# upduino_v2_1_release.net
KiCad netlist of a schematic drawn in EAGLE
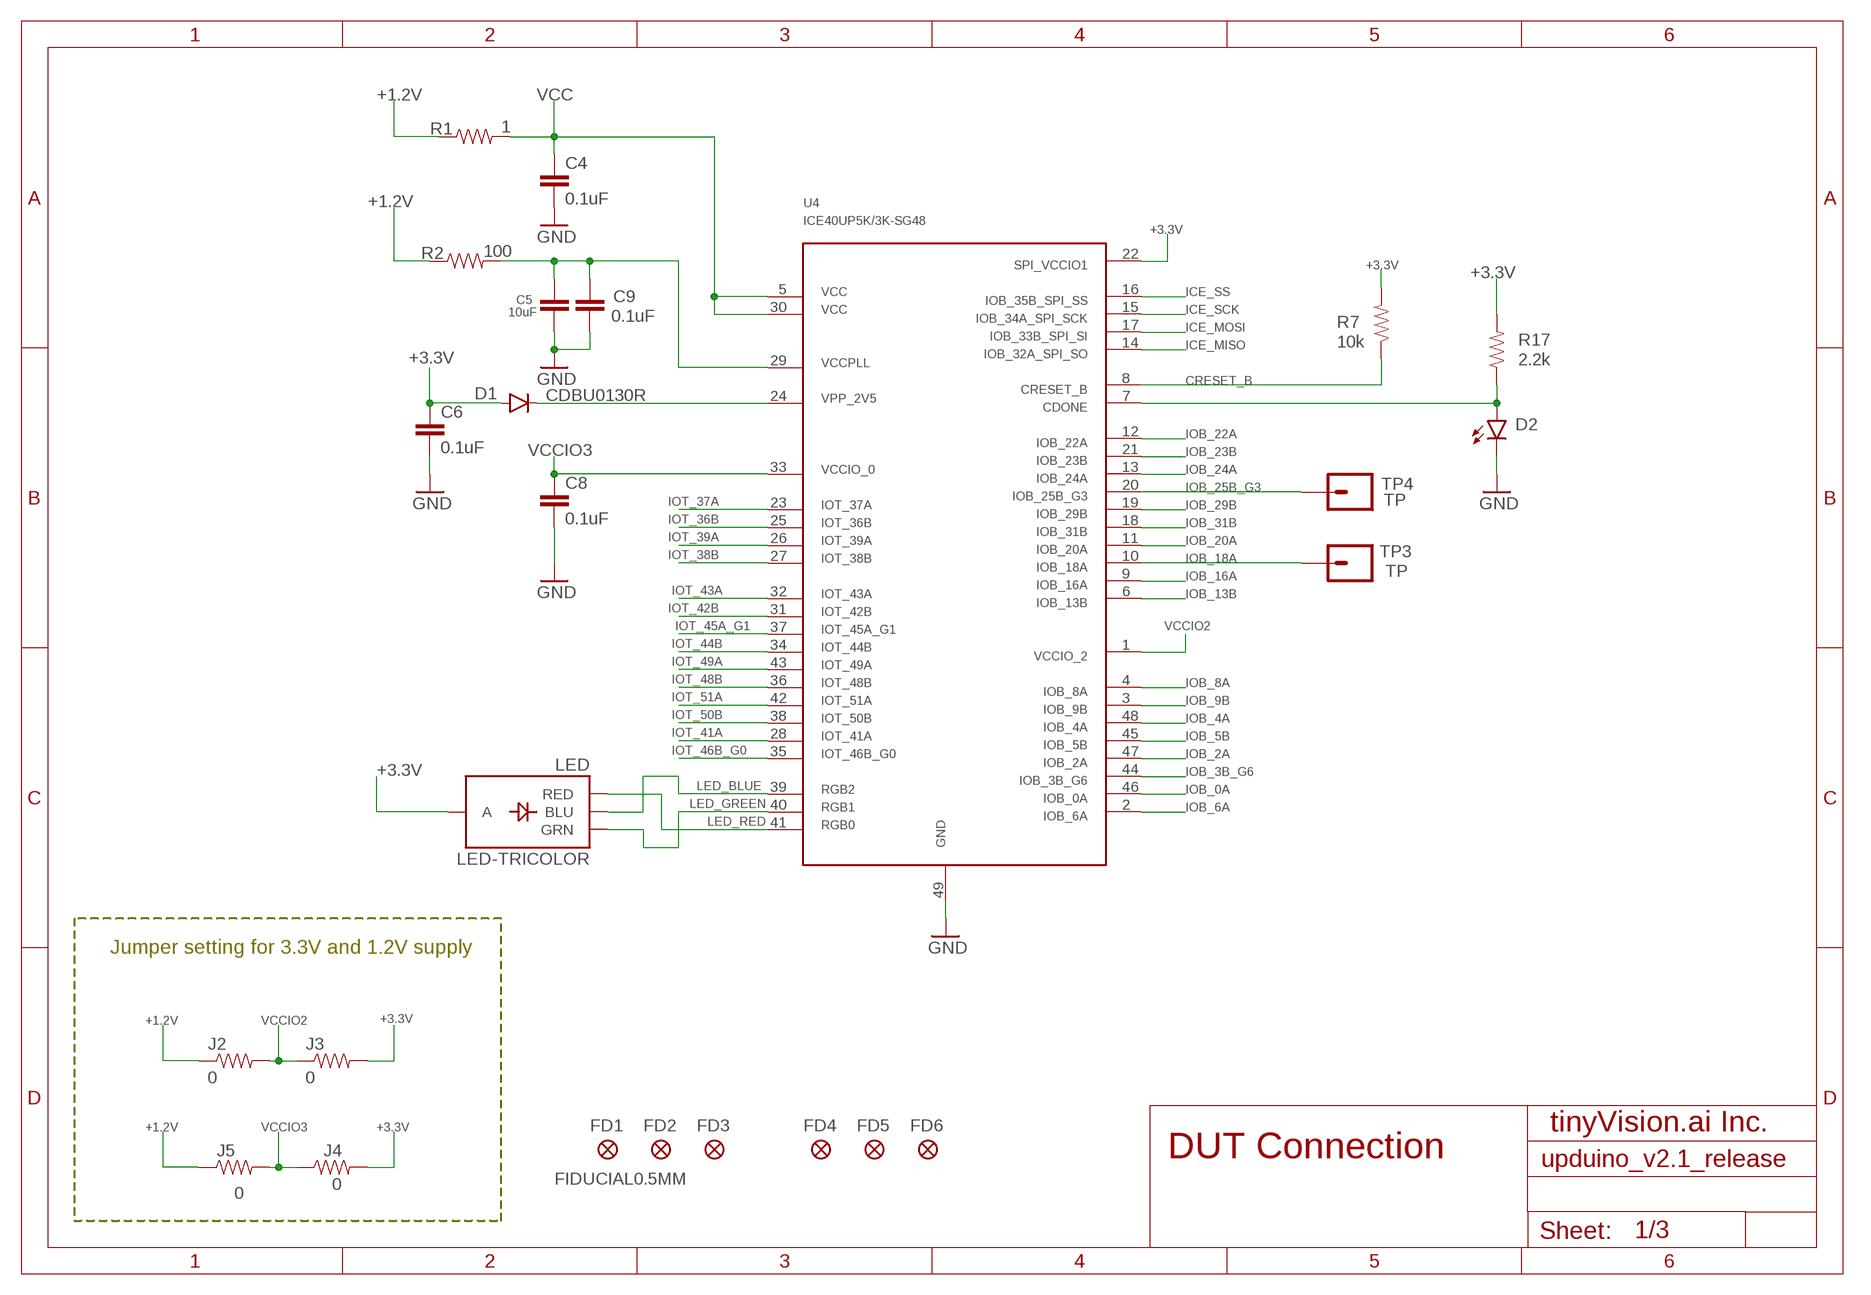
[diagram p0: schematic, sheet 1]
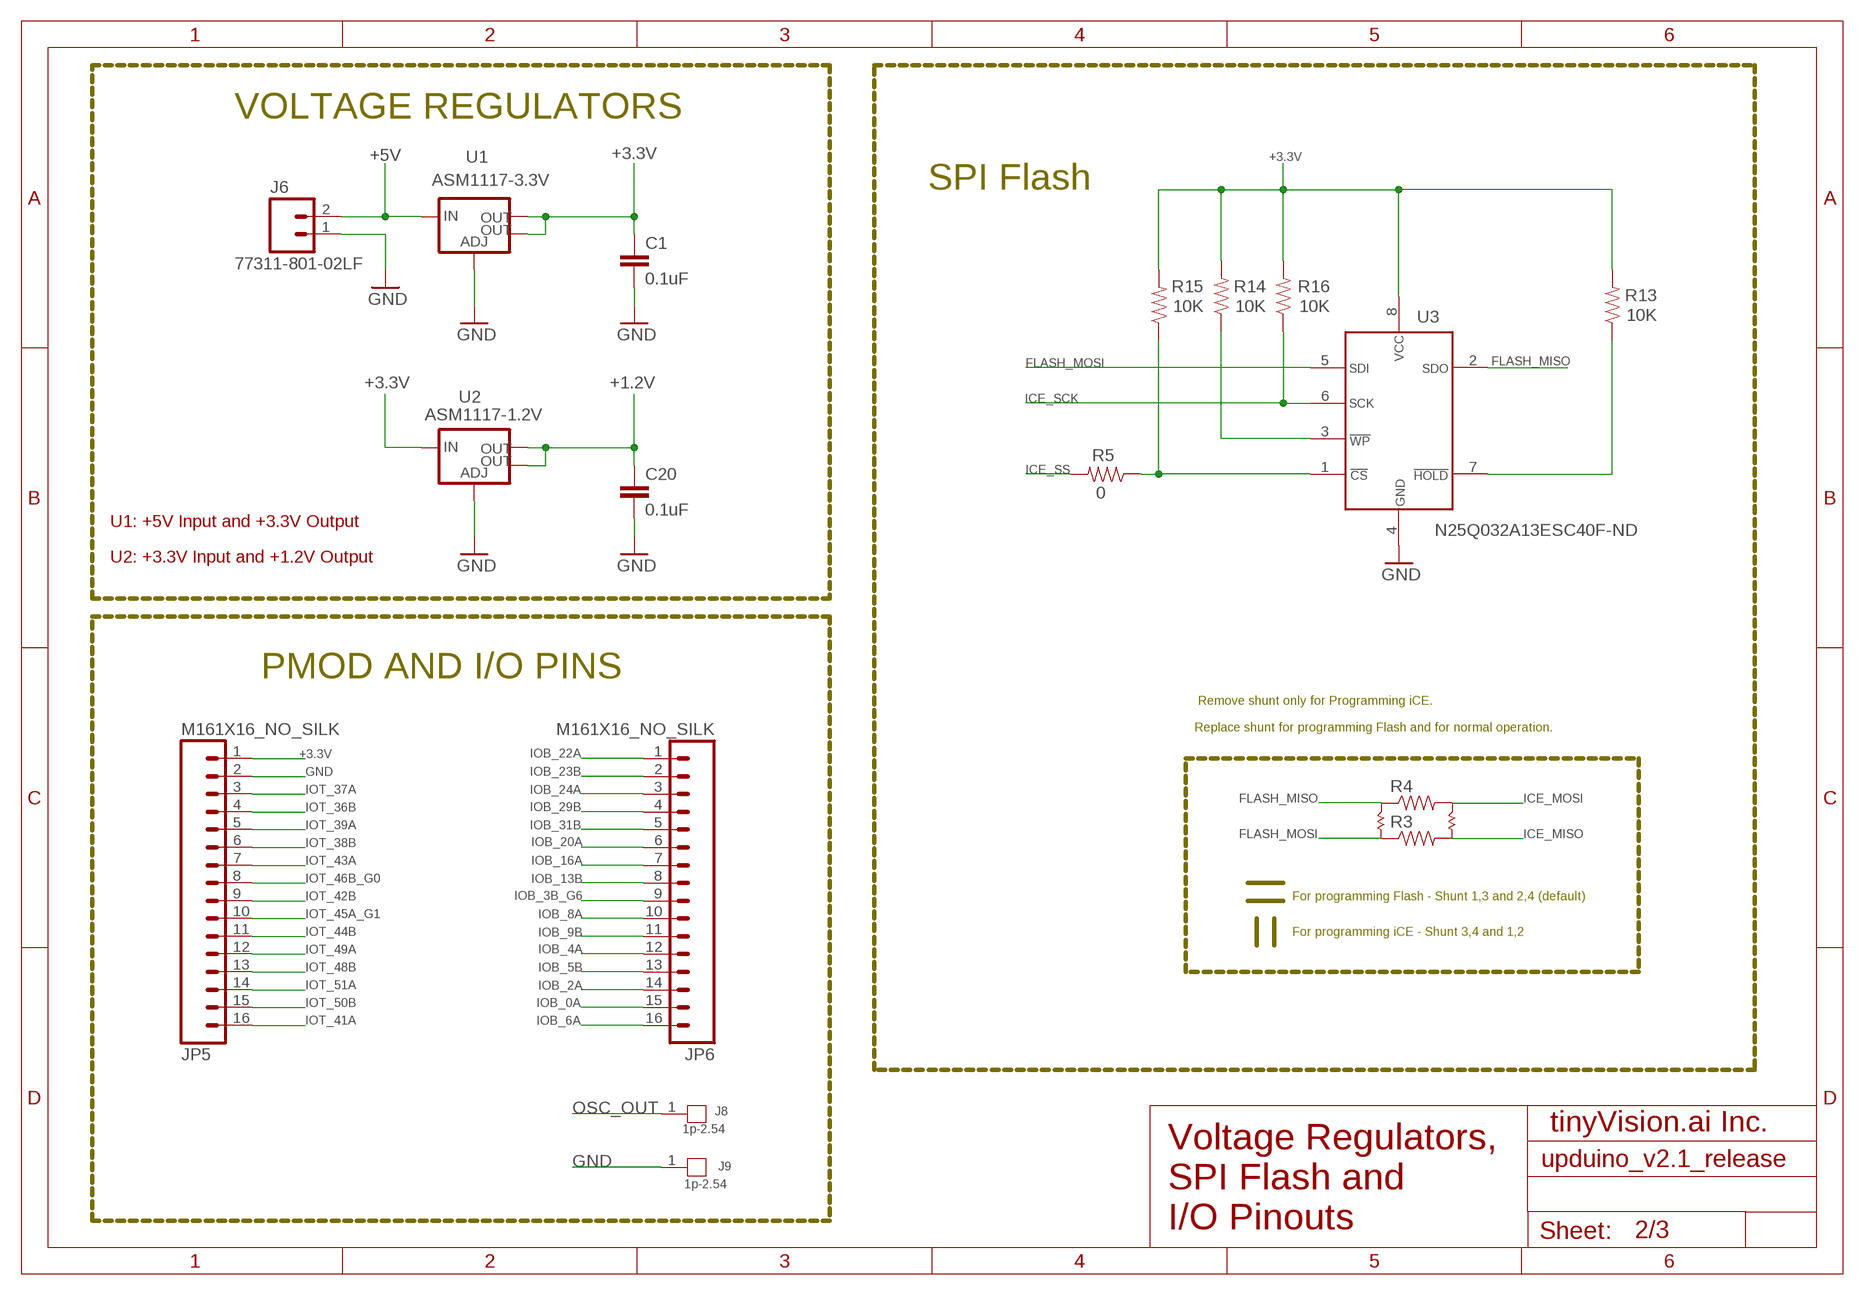
[diagram p1: schematic, sheet 2]
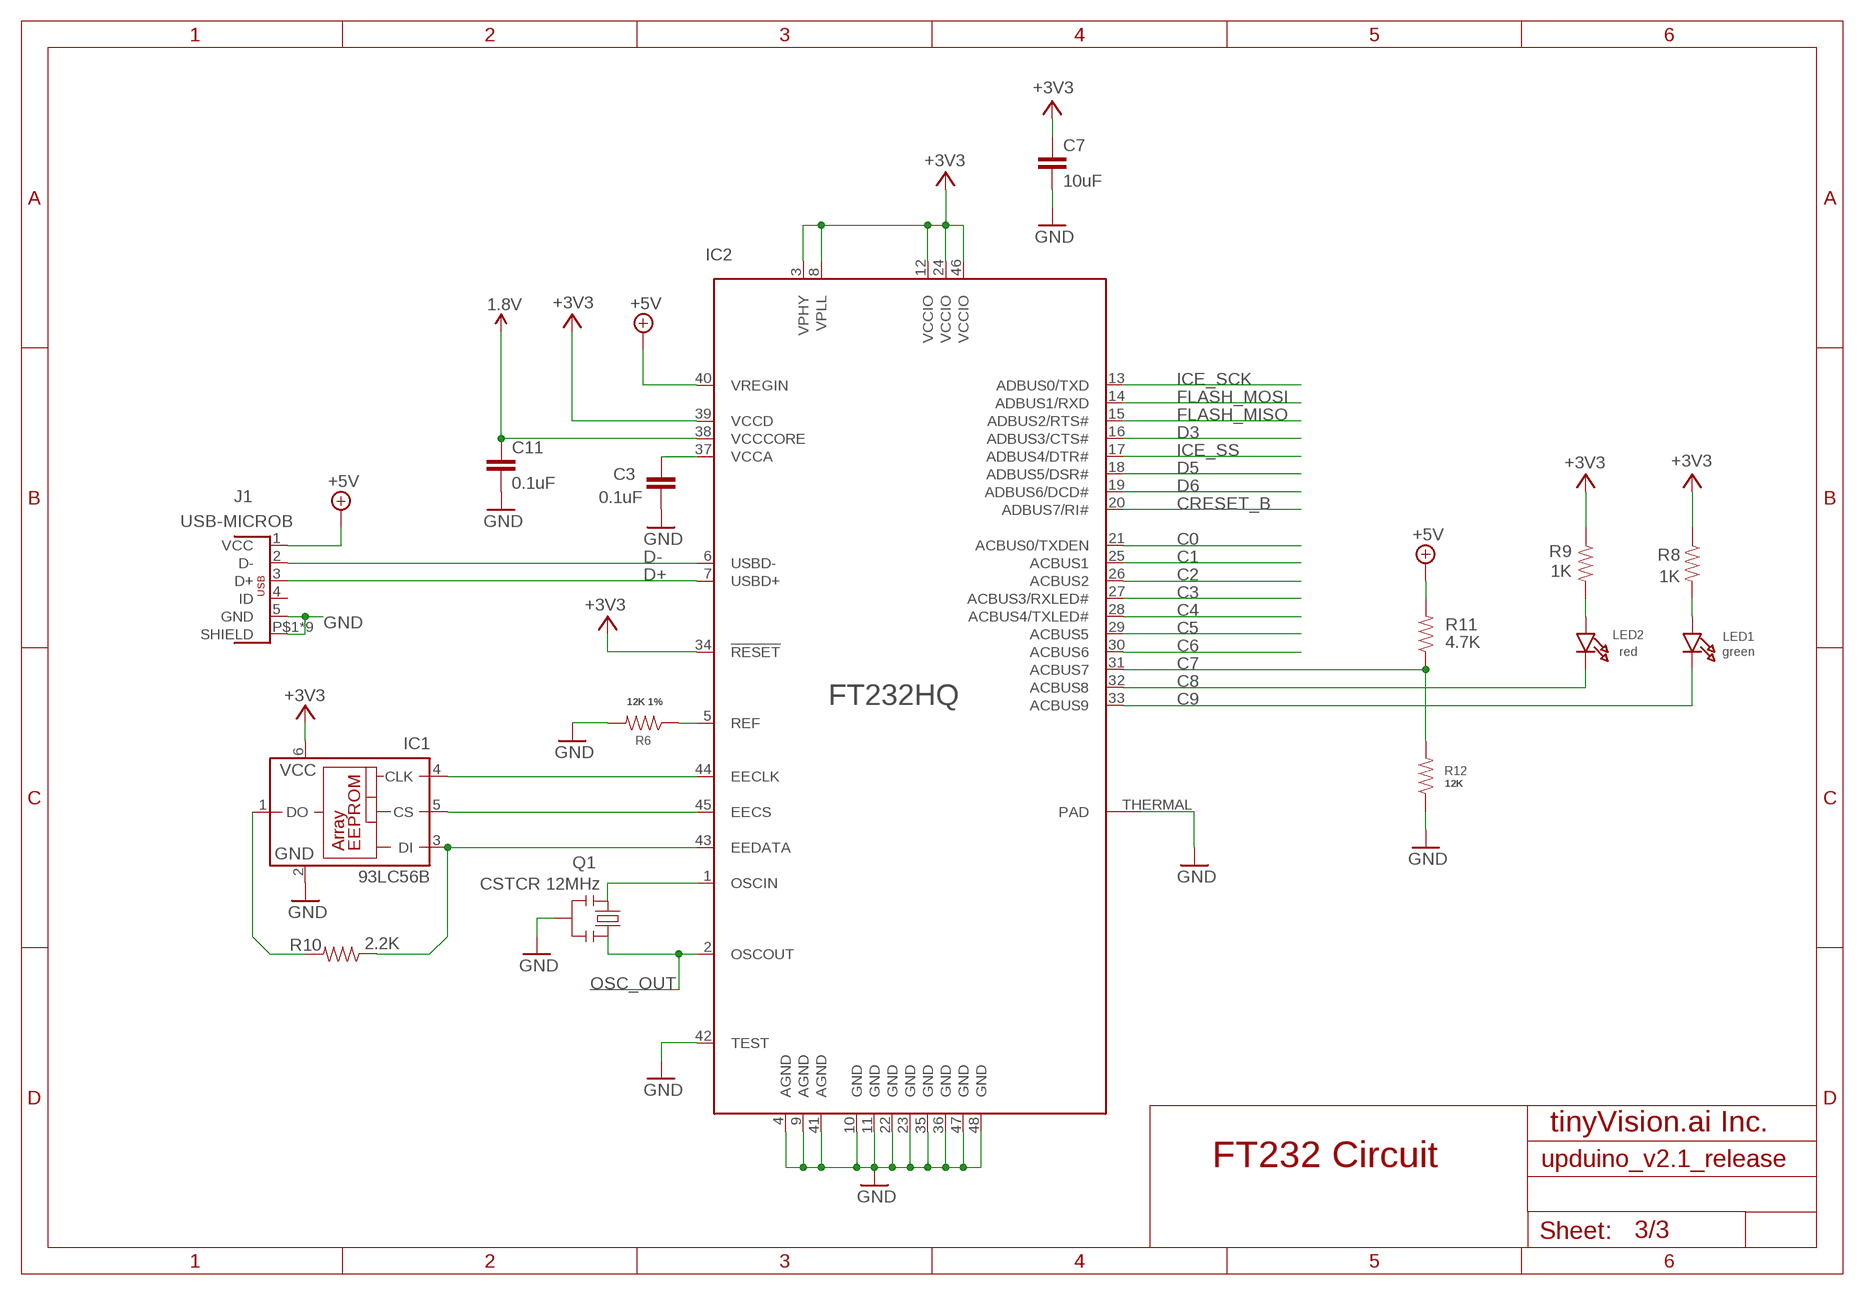
[diagram p2: schematic, sheet 3]

(export (version "E")
  (design (tool "Eeschema 10.0.6"))
  (components
    (comp (ref "C1")
      (value "0.1uF")
      (footprint "eagle-import:0603-CAP")
      (libsource (lib "eagle-import") (part "CAP0603-CAP"))
    )
    (comp (ref "C20")
      (value "0.1uF")
      (footprint "eagle-import:0603-CAP")
      (libsource (lib "eagle-import") (part "CAP0603-CAP"))
    )
    (comp (ref "J6")
      (value "77311-801-02LF")
      (footprint "eagle-import:1X02")
      (libsource (lib "eagle-import") (part "M02PTH"))
    )
    (comp (ref "J8")
      (value "1p-2.54")
      (footprint "eagle-import:1P-65_35MIL")
      (fields (field (name "MPN") "RF130-1013BBS0741"))
      (libsource (lib "eagle-import") (part "DIP-BLACK-ROUND-FEMALE-HEADER-VERT(1P-2.54)"))
    )
    (comp (ref "J9")
      (value "1p-2.54")
      (footprint "eagle-import:1P-65_35MIL")
      (fields (field (name "MPN") "RF130-1013BBS0741"))
      (libsource (lib "eagle-import") (part "DIP-BLACK-ROUND-FEMALE-HEADER-VERT(1P-2.54)"))
    )
    (comp (ref "JP5")
      (value "M161X16_NO_SILK")
      (footprint "eagle-import:1X16_NO_SILK")
      (libsource (lib "eagle-import") (part "M161X16_NO_SILK"))
    )
    (comp (ref "JP6")
      (value "M161X16_NO_SILK")
      (footprint "eagle-import:1X16_NO_SILK")
      (libsource (lib "eagle-import") (part "M161X16_NO_SILK"))
    )
    (comp (ref "R3")
      (value "RESISTOR0603")
      (footprint "eagle-import:0603-RES")
      (libsource (lib "eagle-import") (part "gtjennings_pcb_121217_1200_release_RESISTOR0603"))
    )
    (comp (ref "R4")
      (value "RESISTOR0603")
      (footprint "eagle-import:0603-RES")
      (libsource (lib "eagle-import") (part "gtjennings_pcb_121217_1200_release_RESISTOR0603"))
    )
    (comp (ref "R5")
      (value "0")
      (footprint "eagle-import:0603-RES")
      (libsource (lib "eagle-import") (part "gtjennings_pcb_121217_1200_release_RESISTOR0603"))
    )
    (comp (ref "R13")
      (value "10K")
      (footprint "eagle-import:0603-RES")
      (libsource (lib "eagle-import") (part "RESISTOR0603-RES"))
    )
    (comp (ref "R14")
      (value "10K")
      (footprint "eagle-import:0603-RES")
      (libsource (lib "eagle-import") (part "RESISTOR0603-RES"))
    )
    (comp (ref "R15")
      (value "10K")
      (footprint "eagle-import:0603-RES")
      (libsource (lib "eagle-import") (part "RESISTOR0603-RES"))
    )
    (comp (ref "R16")
      (value "10K")
      (footprint "eagle-import:0603-RES")
      (libsource (lib "eagle-import") (part "RESISTOR0603-RES"))
    )
    (comp (ref "U1")
      (value "ASM1117-3.3V")
      (footprint "eagle-import:SOT223")
      (libsource (lib "eagle-import") (part "V_REG_LM1117SOT223"))
    )
    (comp (ref "U2")
      (value "ASM1117-1.2V")
      (footprint "eagle-import:SOT223")
      (libsource (lib "eagle-import") (part "V_REG_LM1117SOT223"))
    )
    (comp (ref "U3")
      (value "N25Q032A13ESC40F-ND")
      (footprint "eagle-import:SO8")
      (fields (field (name "MPN") "N25Q032A13ESC40F-ND"))
      (libsource (lib "eagle-import") (part "N25Q032A13ESC40F-ND"))
    )
    (comp (ref "C3")
      (value "0.1uF")
      (footprint "eagle-import:0603-CAP")
      (libsource (lib "eagle-import") (part "CAP0603-CAP"))
    )
    (comp (ref "C7")
      (value "10uF")
      (footprint "eagle-import:0603-CAP")
      (libsource (lib "eagle-import") (part "CAP0603-CAP"))
    )
    (comp (ref "C11")
      (value "0.1uF")
      (footprint "eagle-import:0603-CAP")
      (libsource (lib "eagle-import") (part "CAP0603-CAP"))
    )
    (comp (ref "IC1")
      (value "93LC56B")
      (footprint "eagle-import:SOT23-6")
      (fields (field (name "MF") "MICROCHIP") (field (name "MPN") "93LC76AT-I/OT"))
      (libsource (lib "eagle-import") (part "9376?ALC"))
    )
    (comp (ref "IC2")
      (value "FT232HQ")
      (footprint "eagle-import:QFN48_8MM")
      (libsource (lib "eagle-import") (part "FT232HQ"))
    )
    (comp (ref "J1")
      (value "USB-MICROB")
      (footprint "eagle-import:USB_MICROB_10118194-0001LF")
      (libsource (lib "eagle-import") (part "USB-MICROB"))
    )
    (comp (ref "LED1")
      (value "green")
      (footprint "eagle-import:CHIPLED_0805_NOOUTLINE")
      (libsource (lib "eagle-import") (part "LED0805_NOOUTLINE"))
    )
    (comp (ref "LED2")
      (value "red")
      (footprint "eagle-import:CHIPLED_0805_NOOUTLINE")
      (libsource (lib "eagle-import") (part "LED0805_NOOUTLINE"))
    )
    (comp (ref "Q1")
      (value "CSTCR 12MHz")
      (footprint "eagle-import:RESONATOR-SMD")
      (libsource (lib "eagle-import") (part "RESONATORSMD"))
    )
    (comp (ref "R6")
      (value "12K 1%")
      (footprint "eagle-import:0603-RES")
      (libsource (lib "eagle-import") (part "gtjennings_pcb_121217_1200_release_RESISTOR0603"))
    )
    (comp (ref "R8")
      (value "1K")
      (footprint "eagle-import:0603-RES")
      (libsource (lib "eagle-import") (part "gtjennings_pcb_121217_1200_release_RESISTOR0603"))
    )
    (comp (ref "R9")
      (value "1K")
      (footprint "eagle-import:0603-RES")
      (libsource (lib "eagle-import") (part "gtjennings_pcb_121217_1200_release_RESISTOR0603"))
    )
    (comp (ref "R10")
      (value "2.2K")
      (footprint "eagle-import:0603-RES")
      (libsource (lib "eagle-import") (part "gtjennings_pcb_121217_1200_release_RESISTOR0603"))
    )
    (comp (ref "R11")
      (value "4.7K")
      (footprint "eagle-import:0603-RES")
      (libsource (lib "eagle-import") (part "gtjennings_pcb_121217_1200_release_RESISTOR0603"))
    )
    (comp (ref "R12")
      (value "12K")
      (footprint "eagle-import:0603-RES")
      (libsource (lib "eagle-import") (part "gtjennings_pcb_121217_1200_release_RESISTOR0603"))
    )
    (comp (ref "C4")
      (value "0.1uF")
      (footprint "eagle-import:0603-CAP")
      (libsource (lib "eagle-import") (part "CAP0603-CAP"))
    )
    (comp (ref "C5")
      (value "10uF")
      (footprint "eagle-import:0603-CAP")
      (libsource (lib "eagle-import") (part "CAP0603-CAP"))
    )
    (comp (ref "C6")
      (value "0.1uF")
      (footprint "eagle-import:0603-CAP")
      (libsource (lib "eagle-import") (part "CAP0603-CAP"))
    )
    (comp (ref "C8")
      (value "0.1uF")
      (footprint "eagle-import:0603-CAP")
      (libsource (lib "eagle-import") (part "CAP0603-CAP"))
    )
    (comp (ref "C9")
      (value "0.1uF")
      (footprint "eagle-import:0603-CAP")
      (libsource (lib "eagle-import") (part "CAP0603-CAP"))
    )
    (comp (ref "D1")
      (value "CDBU0130R")
      (footprint "eagle-import:SOD523")
      (libsource (lib "eagle-import") (part "DIODE1"))
    )
    (comp (ref "D2")
      (value "LED0603")
      (footprint "eagle-import:LED-0603")
      (libsource (lib "eagle-import") (part "LED0603"))
    )
    (comp (ref "FD1")
      (value "FIDUCIAL0.5MM")
      (footprint "eagle-import:FIDUCIAL_0.5MM")
      (libsource (lib "eagle-import") (part "FIDUCIAL0.5MM"))
    )
    (comp (ref "FD2")
      (value "FIDUCIAL0.5MM")
      (footprint "eagle-import:FIDUCIAL_0.5MM")
      (libsource (lib "eagle-import") (part "FIDUCIAL0.5MM"))
    )
    (comp (ref "FD3")
      (value "FIDUCIAL0.5MM")
      (footprint "eagle-import:FIDUCIAL_0.5MM")
      (libsource (lib "eagle-import") (part "FIDUCIAL0.5MM"))
    )
    (comp (ref "FD4")
      (value "FIDUCIAL0.5MM")
      (footprint "eagle-import:FIDUCIAL_0.5MM")
      (libsource (lib "eagle-import") (part "FIDUCIAL0.5MM"))
    )
    (comp (ref "FD5")
      (value "FIDUCIAL0.5MM")
      (footprint "eagle-import:FIDUCIAL_0.5MM")
      (libsource (lib "eagle-import") (part "FIDUCIAL0.5MM"))
    )
    (comp (ref "FD6")
      (value "FIDUCIAL0.5MM")
      (footprint "eagle-import:FIDUCIAL_0.5MM")
      (libsource (lib "eagle-import") (part "FIDUCIAL0.5MM"))
    )
    (comp (ref "J2")
      (value "0")
      (footprint "eagle-import:0603-RES")
      (libsource (lib "eagle-import") (part "RESISTOR0603-RES"))
    )
    (comp (ref "J3")
      (value "0")
      (footprint "eagle-import:0603-RES")
      (libsource (lib "eagle-import") (part "RESISTOR0603-RES"))
    )
    (comp (ref "J4")
      (value "0")
      (footprint "eagle-import:0603-RES")
      (libsource (lib "eagle-import") (part "RESISTOR0603-RES"))
    )
    (comp (ref "J5")
      (value "0")
      (footprint "eagle-import:0603-RES")
      (libsource (lib "eagle-import") (part "RESISTOR0603-RES"))
    )
    (comp (ref "LED")
      (value "LED-TRICOLOR")
      (footprint "eagle-import:LED-TRICOLOR-SMD")
      (libsource (lib "eagle-import") (part "LED-TRICOLOR"))
    )
    (comp (ref "R1")
      (value "1")
      (footprint "eagle-import:0603-RES")
      (libsource (lib "eagle-import") (part "RESISTOR0603-RES"))
    )
    (comp (ref "R2")
      (value "100")
      (footprint "eagle-import:0603-RES")
      (libsource (lib "eagle-import") (part "RESISTOR0603-RES"))
    )
    (comp (ref "R7")
      (value "10k")
      (footprint "eagle-import:0603-RES")
      (libsource (lib "eagle-import") (part "RESISTOR0603-RES"))
    )
    (comp (ref "R17")
      (value "2.2k")
      (footprint "eagle-import:0603-RES")
      (libsource (lib "eagle-import") (part "RESISTOR0603-RES"))
    )
    (comp (ref "TP3") (value "TP") (footprint "eagle-import:TP") (libsource (lib "eagle-import") (part "TP")))
    (comp (ref "TP4") (value "TP") (footprint "eagle-import:TP") (libsource (lib "eagle-import") (part "TP")))
    (comp (ref "U4")
      (value "ICE40UP5K/3K-SG48")
      (footprint "eagle-import:ICE40UP5K_3K-SG48")
      (libsource (lib "eagle-import") (part "ICE40UP5K/3K-SG48"))
    )
  )
  (nets
    (net (code "1") (name "+1.2V") (class "Default")
      (node (ref "C20") (pin "1") (pinfunction "1_1") (pintype "passive"))
      (node (ref "J2") (pin "1") (pinfunction "1_1") (pintype "passive"))
      (node (ref "J5") (pin "1") (pinfunction "1_1") (pintype "passive"))
      (node (ref "R1") (pin "1") (pinfunction "1_1") (pintype "passive"))
      (node (ref "R2") (pin "1") (pinfunction "1_1") (pintype "passive"))
      (node (ref "U2") (pin "2") (pinfunction "OUT_2") (pintype "output"))
      (node (ref "U2") (pin "4") (pinfunction "OUT_4") (pintype "output"))
    )
    (net (code "2") (name "+3.3V") (class "Default")
      (node (ref "C1") (pin "1") (pinfunction "1_1") (pintype "passive"))
      (node (ref "C6") (pin "1") (pinfunction "1_1") (pintype "passive"))
      (node (ref "D1") (pin "A") (pinfunction "A_A") (pintype "passive"))
      (node (ref "J3") (pin "2") (pinfunction "2_2") (pintype "passive"))
      (node (ref "J4") (pin "2") (pinfunction "2_2") (pintype "passive"))
      (node (ref "JP5") (pin "1") (pinfunction "1_1") (pintype "passive"))
      (node (ref "LED") (pin "A") (pinfunction "A_A") (pintype "bidirectional"))
      (node (ref "R13") (pin "2") (pinfunction "2_2") (pintype "passive"))
      (node (ref "R14") (pin "2") (pinfunction "2_2") (pintype "passive"))
      (node (ref "R15") (pin "2") (pinfunction "2_2") (pintype "passive"))
      (node (ref "R16") (pin "2") (pinfunction "2_2") (pintype "passive"))
      (node (ref "R17") (pin "2") (pinfunction "2_2") (pintype "passive"))
      (node (ref "R7") (pin "2") (pinfunction "2_2") (pintype "passive"))
      (node (ref "U1") (pin "2") (pinfunction "OUT_2") (pintype "output"))
      (node (ref "U1") (pin "4") (pinfunction "OUT_4") (pintype "output"))
      (node (ref "U2") (pin "3") (pinfunction "IN_3") (pintype "input"))
      (node (ref "U3") (pin "8") (pinfunction "8_8") (pintype "bidirectional"))
      (node (ref "U4") (pin "22") (pinfunction "22_22") (pintype "bidirectional"))
    )
    (net (code "3") (name "+3V3") (class "Default")
      (node (ref "C7") (pin "1") (pinfunction "1_1") (pintype "passive"))
      (node (ref "IC1") (pin "6") (pinfunction "VCC_6") (pintype "power_in"))
      (node (ref "IC2") (pin "12") (pinfunction "VCCIO_12") (pintype "power_in"))
      (node (ref "IC2") (pin "24") (pinfunction "VCCIO_24") (pintype "power_in"))
      (node (ref "IC2") (pin "3") (pinfunction "VPHY_3") (pintype "power_in"))
      (node (ref "IC2") (pin "34") (pinfunction "~{RESET}_34") (pintype "input"))
      (node (ref "IC2") (pin "39") (pinfunction "VCCD_39") (pintype "power_in"))
      (node (ref "IC2") (pin "46") (pinfunction "VCCIO_46") (pintype "power_in"))
      (node (ref "IC2") (pin "8") (pinfunction "VPLL_8") (pintype "power_in"))
      (node (ref "R8") (pin "1") (pinfunction "1_1") (pintype "passive"))
      (node (ref "R9") (pin "1") (pinfunction "1_1") (pintype "passive"))
    )
    (net (code "4") (name "+5V") (class "Default")
      (node (ref "IC2") (pin "40") (pinfunction "VREGIN_40") (pintype "power_in"))
      (node (ref "J1") (pin "1") (pinfunction "VCC_1") (pintype "bidirectional"))
      (node (ref "J6") (pin "2") (pinfunction "2_2") (pintype "passive"))
      (node (ref "R11") (pin "2") (pinfunction "2_2") (pintype "passive"))
      (node (ref "U1") (pin "3") (pinfunction "IN_3") (pintype "input"))
    )
    (net (code "5") (name "1.8V") (class "Default")
      (node (ref "C11") (pin "1") (pinfunction "1_1") (pintype "passive"))
      (node (ref "IC2") (pin "38") (pinfunction "VCCCORE_38") (pintype "power_in"))
    )
    (net (code "6") (name "C0") (class "Default")
      (node (ref "IC2") (pin "21") (pinfunction "ACBUS0/TXDEN_21") (pintype "bidirectional"))
    )
    (net (code "7") (name "C1") (class "Default")
      (node (ref "IC2") (pin "25") (pinfunction "ACBUS1_25") (pintype "bidirectional"))
    )
    (net (code "8") (name "C2") (class "Default")
      (node (ref "IC2") (pin "26") (pinfunction "ACBUS2_26") (pintype "bidirectional"))
    )
    (net (code "9") (name "C3") (class "Default")
      (node (ref "IC2") (pin "27") (pinfunction "ACBUS3/RXLED#_27") (pintype "bidirectional"))
    )
    (net (code "10") (name "C4") (class "Default")
      (node (ref "IC2") (pin "28") (pinfunction "ACBUS4/TXLED#_28") (pintype "bidirectional"))
    )
    (net (code "11") (name "C5") (class "Default")
      (node (ref "IC2") (pin "29") (pinfunction "ACBUS5_29") (pintype "bidirectional"))
    )
    (net (code "12") (name "C6") (class "Default")
      (node (ref "IC2") (pin "30") (pinfunction "ACBUS6_30") (pintype "bidirectional"))
    )
    (net (code "13") (name "C7") (class "Default")
      (node (ref "IC2") (pin "31") (pinfunction "ACBUS7_31") (pintype "bidirectional"))
      (node (ref "R11") (pin "1") (pinfunction "1_1") (pintype "passive"))
      (node (ref "R12") (pin "2") (pinfunction "2_2") (pintype "passive"))
    )
    (net (code "14") (name "C8") (class "Default")
      (node (ref "IC2") (pin "32") (pinfunction "ACBUS8_32") (pintype "bidirectional"))
      (node (ref "LED2") (pin "C") (pinfunction "C_C") (pintype "passive"))
    )
    (net (code "15") (name "C9") (class "Default")
      (node (ref "IC2") (pin "33") (pinfunction "ACBUS9_33") (pintype "bidirectional"))
      (node (ref "LED1") (pin "C") (pinfunction "C_C") (pintype "passive"))
    )
    (net (code "16") (name "CRESET_B") (class "Default")
      (node (ref "IC2") (pin "20") (pinfunction "ADBUS7/RI#_20") (pintype "input"))
      (node (ref "R7") (pin "1") (pinfunction "1_1") (pintype "passive"))
      (node (ref "U4") (pin "8") (pinfunction "8_8") (pintype "bidirectional"))
    )
    (net (code "17") (name "D+") (class "Default")
      (node (ref "IC2") (pin "7") (pinfunction "USBD+_7") (pintype "bidirectional"))
      (node (ref "J1") (pin "3") (pinfunction "D+_3") (pintype "bidirectional"))
    )
    (net (code "18") (name "D-") (class "Default")
      (node (ref "IC2") (pin "6") (pinfunction "USBD-_6") (pintype "bidirectional"))
      (node (ref "J1") (pin "2") (pinfunction "D-_2") (pintype "bidirectional"))
    )
    (net (code "19") (name "D3") (class "Default")
      (node (ref "IC2") (pin "16") (pinfunction "ADBUS3/CTS#_16") (pintype "input"))
    )
    (net (code "20") (name "D5") (class "Default")
      (node (ref "IC2") (pin "18") (pinfunction "ADBUS5/DSR#_18") (pintype "input"))
    )
    (net (code "21") (name "D6") (class "Default")
      (node (ref "IC2") (pin "19") (pinfunction "ADBUS6/DCD#_19") (pintype "input"))
    )
    (net (code "22") (name "FLASH_MISO") (class "Default")
      (node (ref "IC2") (pin "15") (pinfunction "ADBUS2/RTS#_15") (pintype "output"))
      (node (ref "R4") (pin "1") (pinfunction "1_1") (pintype "passive"))
      (node (ref "U3") (pin "2") (pinfunction "2_2") (pintype "bidirectional"))
    )
    (net (code "23") (name "FLASH_MOSI") (class "Default")
      (node (ref "IC2") (pin "14") (pinfunction "ADBUS1/RXD_14") (pintype "input"))
      (node (ref "R3") (pin "1") (pinfunction "1_1") (pintype "passive"))
      (node (ref "U3") (pin "5") (pinfunction "5_5") (pintype "bidirectional"))
    )
    (net (code "24") (name "GND") (class "Default")
      (node (ref "C1") (pin "2") (pinfunction "2_2") (pintype "passive"))
      (node (ref "C11") (pin "2") (pinfunction "2_2") (pintype "passive"))
      (node (ref "C20") (pin "2") (pinfunction "2_2") (pintype "passive"))
      (node (ref "C3") (pin "2") (pinfunction "2_2") (pintype "passive"))
      (node (ref "C4") (pin "2") (pinfunction "2_2") (pintype "passive"))
      (node (ref "C5") (pin "2") (pinfunction "2_2") (pintype "passive"))
      (node (ref "C6") (pin "2") (pinfunction "2_2") (pintype "passive"))
      (node (ref "C7") (pin "2") (pinfunction "2_2") (pintype "passive"))
      (node (ref "C8") (pin "2") (pinfunction "2_2") (pintype "passive"))
      (node (ref "C9") (pin "2") (pinfunction "2_2") (pintype "passive"))
      (node (ref "D2") (pin "C") (pinfunction "C_C") (pintype "passive"))
      (node (ref "IC1") (pin "2") (pinfunction "GND_2") (pintype "power_in"))
      (node (ref "IC2") (pin "10") (pinfunction "GND_10") (pintype "power_in"))
      (node (ref "IC2") (pin "11") (pinfunction "GND_11") (pintype "power_in"))
      (node (ref "IC2") (pin "22") (pinfunction "GND_22") (pintype "power_in"))
      (node (ref "IC2") (pin "23") (pinfunction "GND_23") (pintype "power_in"))
      (node (ref "IC2") (pin "35") (pinfunction "GND_35") (pintype "power_in"))
      (node (ref "IC2") (pin "36") (pinfunction "GND_36") (pintype "power_in"))
      (node (ref "IC2") (pin "4") (pinfunction "AGND_4") (pintype "power_in"))
      (node (ref "IC2") (pin "41") (pinfunction "AGND_41") (pintype "power_in"))
      (node (ref "IC2") (pin "42") (pinfunction "TEST_42") (pintype "input"))
      (node (ref "IC2") (pin "47") (pinfunction "GND_47") (pintype "power_in"))
      (node (ref "IC2") (pin "48") (pinfunction "GND_48") (pintype "power_in"))
      (node (ref "IC2") (pin "9") (pinfunction "AGND_9") (pintype "power_in"))
      (node (ref "IC2") (pin "THERMAL") (pinfunction "PAD_THERMAL") (pintype "passive"))
      (node (ref "J1") (pin "5") (pinfunction "GND_5") (pintype "bidirectional"))
      (node (ref "J1") (pin "P$1") (pinfunction "SHIELD_P$1") (pintype "bidirectional"))
      (node (ref "J1") (pin "P$2") (pinfunction "SHIELD_P$2") (pintype "bidirectional"))
      (node (ref "J1") (pin "P$3") (pinfunction "SHIELD_P$3") (pintype "bidirectional"))
      (node (ref "J1") (pin "P$4") (pinfunction "SHIELD_P$4") (pintype "bidirectional"))
      (node (ref "J1") (pin "P$5") (pinfunction "SHIELD_P$5") (pintype "bidirectional"))
      (node (ref "J1") (pin "P@1") (pinfunction "SHIELD_P@1") (pintype "bidirectional"))
      (node (ref "J1") (pin "P@2") (pinfunction "SHIELD_P@2") (pintype "bidirectional"))
      (node (ref "J1") (pin "P@3") (pinfunction "SHIELD_P@3") (pintype "bidirectional"))
      (node (ref "J1") (pin "P@4") (pinfunction "SHIELD_P@4") (pintype "bidirectional"))
      (node (ref "J6") (pin "1") (pinfunction "1_1") (pintype "passive"))
      (node (ref "J9") (pin "1") (pinfunction "1_1") (pintype "bidirectional"))
      (node (ref "JP5") (pin "2") (pinfunction "2_2") (pintype "passive"))
      (node (ref "Q1") (pin "2") (pinfunction "2_2") (pintype "passive"))
      (node (ref "R12") (pin "1") (pinfunction "1_1") (pintype "passive"))
      (node (ref "R6") (pin "2") (pinfunction "2_2") (pintype "passive"))
      (node (ref "U1") (pin "1") (pinfunction "ADJ_1") (pintype "input"))
      (node (ref "U2") (pin "1") (pinfunction "ADJ_1") (pintype "input"))
      (node (ref "U3") (pin "4") (pinfunction "4_4") (pintype "bidirectional"))
      (node (ref "U4") (pin "49") (pinfunction "49_49") (pintype "bidirectional"))
    )
    (net (code "25") (name "ICE_MISO") (class "Default")
      (node (ref "R3") (pin "2") (pinfunction "2_2") (pintype "passive"))
      (node (ref "U4") (pin "14") (pinfunction "14_14") (pintype "bidirectional"))
    )
    (net (code "26") (name "ICE_MOSI") (class "Default")
      (node (ref "R4") (pin "2") (pinfunction "2_2") (pintype "passive"))
      (node (ref "U4") (pin "17") (pinfunction "17_17") (pintype "bidirectional"))
    )
    (net (code "27") (name "ICE_SCK") (class "Default")
      (node (ref "IC2") (pin "13") (pinfunction "ADBUS0/TXD_13") (pintype "output"))
      (node (ref "R16") (pin "1") (pinfunction "1_1") (pintype "passive"))
      (node (ref "U3") (pin "6") (pinfunction "6_6") (pintype "bidirectional"))
      (node (ref "U4") (pin "15") (pinfunction "15_15") (pintype "bidirectional"))
    )
    (net (code "28") (name "ICE_SS") (class "Default")
      (node (ref "IC2") (pin "17") (pinfunction "ADBUS4/DTR#_17") (pintype "output"))
      (node (ref "R5") (pin "2") (pinfunction "2_2") (pintype "passive"))
      (node (ref "U4") (pin "16") (pinfunction "16_16") (pintype "bidirectional"))
    )
    (net (code "29") (name "IOB_0A") (class "Default")
      (node (ref "JP6") (pin "15") (pinfunction "15_15") (pintype "passive"))
      (node (ref "U4") (pin "46") (pinfunction "46_46") (pintype "bidirectional"))
    )
    (net (code "30") (name "IOB_2A") (class "Default")
      (node (ref "JP6") (pin "14") (pinfunction "14_14") (pintype "passive"))
      (node (ref "U4") (pin "47") (pinfunction "47_47") (pintype "bidirectional"))
    )
    (net (code "31") (name "IOB_3B_G6") (class "Default")
      (node (ref "JP6") (pin "9") (pinfunction "9_9") (pintype "passive"))
      (node (ref "U4") (pin "44") (pinfunction "44_44") (pintype "bidirectional"))
    )
    (net (code "32") (name "IOB_4A") (class "Default")
      (node (ref "JP6") (pin "12") (pinfunction "12_12") (pintype "passive"))
      (node (ref "U4") (pin "48") (pinfunction "48_48") (pintype "bidirectional"))
    )
    (net (code "33") (name "IOB_5B") (class "Default")
      (node (ref "JP6") (pin "13") (pinfunction "13_13") (pintype "passive"))
      (node (ref "U4") (pin "45") (pinfunction "45_45") (pintype "bidirectional"))
    )
    (net (code "34") (name "IOB_6A") (class "Default")
      (node (ref "JP6") (pin "16") (pinfunction "16_16") (pintype "passive"))
      (node (ref "U4") (pin "2") (pinfunction "2_2") (pintype "bidirectional"))
    )
    (net (code "35") (name "IOB_8A") (class "Default")
      (node (ref "JP6") (pin "10") (pinfunction "10_10") (pintype "passive"))
      (node (ref "U4") (pin "4") (pinfunction "4_4") (pintype "bidirectional"))
    )
    (net (code "36") (name "IOB_9B") (class "Default")
      (node (ref "JP6") (pin "11") (pinfunction "11_11") (pintype "passive"))
      (node (ref "U4") (pin "3") (pinfunction "3_3") (pintype "bidirectional"))
    )
    (net (code "37") (name "IOB_13B") (class "Default")
      (node (ref "JP6") (pin "8") (pinfunction "8_8") (pintype "passive"))
      (node (ref "U4") (pin "6") (pinfunction "6_6") (pintype "bidirectional"))
    )
    (net (code "38") (name "IOB_16A") (class "Default")
      (node (ref "JP6") (pin "7") (pinfunction "7_7") (pintype "passive"))
      (node (ref "U4") (pin "9") (pinfunction "9_9") (pintype "bidirectional"))
    )
    (net (code "39") (name "IOB_18A") (class "Default")
      (node (ref "TP3") (pin "1") (pinfunction "1_1") (pintype "passive"))
      (node (ref "U4") (pin "10") (pinfunction "10_10") (pintype "bidirectional"))
    )
    (net (code "40") (name "IOB_20A") (class "Default")
      (node (ref "JP6") (pin "6") (pinfunction "6_6") (pintype "passive"))
      (node (ref "U4") (pin "11") (pinfunction "11_11") (pintype "bidirectional"))
    )
    (net (code "41") (name "IOB_22A") (class "Default")
      (node (ref "JP6") (pin "1") (pinfunction "1_1") (pintype "passive"))
      (node (ref "U4") (pin "12") (pinfunction "12_12") (pintype "bidirectional"))
    )
    (net (code "42") (name "IOB_23B") (class "Default")
      (node (ref "JP6") (pin "2") (pinfunction "2_2") (pintype "passive"))
      (node (ref "U4") (pin "21") (pinfunction "21_21") (pintype "bidirectional"))
    )
    (net (code "43") (name "IOB_24A") (class "Default")
      (node (ref "JP6") (pin "3") (pinfunction "3_3") (pintype "passive"))
      (node (ref "U4") (pin "13") (pinfunction "13_13") (pintype "bidirectional"))
    )
    (net (code "44") (name "IOB_25B_G3") (class "Default")
      (node (ref "TP4") (pin "1") (pinfunction "1_1") (pintype "passive"))
      (node (ref "U4") (pin "20") (pinfunction "20_20") (pintype "bidirectional"))
    )
    (net (code "45") (name "IOB_29B") (class "Default")
      (node (ref "JP6") (pin "4") (pinfunction "4_4") (pintype "passive"))
      (node (ref "U4") (pin "19") (pinfunction "19_19") (pintype "bidirectional"))
    )
    (net (code "46") (name "IOB_31B") (class "Default")
      (node (ref "JP6") (pin "5") (pinfunction "5_5") (pintype "passive"))
      (node (ref "U4") (pin "18") (pinfunction "18_18") (pintype "bidirectional"))
    )
    (net (code "47") (name "IOT_36B") (class "Default")
      (node (ref "JP5") (pin "4") (pinfunction "4_4") (pintype "passive"))
      (node (ref "U4") (pin "25") (pinfunction "25_25") (pintype "bidirectional"))
    )
    (net (code "48") (name "IOT_37A") (class "Default")
      (node (ref "JP5") (pin "3") (pinfunction "3_3") (pintype "passive"))
      (node (ref "U4") (pin "23") (pinfunction "23_23") (pintype "bidirectional"))
    )
    (net (code "49") (name "IOT_38B") (class "Default")
      (node (ref "JP5") (pin "6") (pinfunction "6_6") (pintype "passive"))
      (node (ref "U4") (pin "27") (pinfunction "27_27") (pintype "bidirectional"))
    )
    (net (code "50") (name "IOT_39A") (class "Default")
      (node (ref "JP5") (pin "5") (pinfunction "5_5") (pintype "passive"))
      (node (ref "U4") (pin "26") (pinfunction "26_26") (pintype "bidirectional"))
    )
    (net (code "51") (name "IOT_41A") (class "Default")
      (node (ref "JP5") (pin "16") (pinfunction "16_16") (pintype "passive"))
      (node (ref "U4") (pin "28") (pinfunction "28_28") (pintype "bidirectional"))
    )
    (net (code "52") (name "IOT_42B") (class "Default")
      (node (ref "JP5") (pin "9") (pinfunction "9_9") (pintype "passive"))
      (node (ref "U4") (pin "31") (pinfunction "31_31") (pintype "bidirectional"))
    )
    (net (code "53") (name "IOT_43A") (class "Default")
      (node (ref "JP5") (pin "7") (pinfunction "7_7") (pintype "passive"))
      (node (ref "U4") (pin "32") (pinfunction "32_32") (pintype "bidirectional"))
    )
    (net (code "54") (name "IOT_44B") (class "Default")
      (node (ref "JP5") (pin "11") (pinfunction "11_11") (pintype "passive"))
      (node (ref "U4") (pin "34") (pinfunction "34_34") (pintype "bidirectional"))
    )
    (net (code "55") (name "IOT_45A_G1") (class "Default")
      (node (ref "JP5") (pin "10") (pinfunction "10_10") (pintype "passive"))
      (node (ref "U4") (pin "37") (pinfunction "37_37") (pintype "bidirectional"))
    )
    (net (code "56") (name "IOT_46B_G0") (class "Default")
      (node (ref "JP5") (pin "8") (pinfunction "8_8") (pintype "passive"))
      (node (ref "U4") (pin "35") (pinfunction "35_35") (pintype "bidirectional"))
    )
    (net (code "57") (name "IOT_48B") (class "Default")
      (node (ref "JP5") (pin "13") (pinfunction "13_13") (pintype "passive"))
      (node (ref "U4") (pin "36") (pinfunction "36_36") (pintype "bidirectional"))
    )
    (net (code "58") (name "IOT_49A") (class "Default")
      (node (ref "JP5") (pin "12") (pinfunction "12_12") (pintype "passive"))
      (node (ref "U4") (pin "43") (pinfunction "43_43") (pintype "bidirectional"))
    )
    (net (code "59") (name "IOT_50B") (class "Default")
      (node (ref "JP5") (pin "15") (pinfunction "15_15") (pintype "passive"))
      (node (ref "U4") (pin "38") (pinfunction "38_38") (pintype "bidirectional"))
    )
    (net (code "60") (name "IOT_51A") (class "Default")
      (node (ref "JP5") (pin "14") (pinfunction "14_14") (pintype "passive"))
      (node (ref "U4") (pin "42") (pinfunction "42_42") (pintype "bidirectional"))
    )
    (net (code "61") (name "LED_BLUE") (class "Default")
      (node (ref "LED") (pin "B") (pinfunction "BLU_B") (pintype "bidirectional"))
      (node (ref "U4") (pin "39") (pinfunction "39_39") (pintype "bidirectional"))
    )
    (net (code "62") (name "LED_GREEN") (class "Default")
      (node (ref "LED") (pin "G") (pinfunction "GRN_G") (pintype "bidirectional"))
      (node (ref "U4") (pin "40") (pinfunction "40_40") (pintype "bidirectional"))
    )
    (net (code "63") (name "LED_RED") (class "Default")
      (node (ref "LED") (pin "R") (pinfunction "RED_R") (pintype "bidirectional"))
      (node (ref "U4") (pin "41") (pinfunction "41_41") (pintype "bidirectional"))
    )
    (net (code "64") (name "Net-(C5-Pad1)") (class "Default")
      (node (ref "C5") (pin "1") (pinfunction "1_1") (pintype "passive"))
      (node (ref "C9") (pin "1") (pinfunction "1_1") (pintype "passive"))
      (node (ref "R2") (pin "2") (pinfunction "2_2") (pintype "passive"))
      (node (ref "U4") (pin "29") (pinfunction "29_29") (pintype "bidirectional"))
    )
    (net (code "65") (name "Net-(D1-PadC)") (class "Default")
      (node (ref "D1") (pin "C") (pinfunction "C_C") (pintype "passive"))
      (node (ref "U4") (pin "24") (pinfunction "24_24") (pintype "bidirectional"))
    )
    (net (code "66") (name "Net-(D2-PadA)") (class "Default")
      (node (ref "D2") (pin "A") (pinfunction "A_A") (pintype "passive"))
      (node (ref "R17") (pin "1") (pinfunction "1_1") (pintype "passive"))
      (node (ref "U4") (pin "7") (pinfunction "7_7") (pintype "bidirectional"))
    )
    (net (code "67") (name "Net-(IC1-CLK)") (class "Default")
      (node (ref "IC1") (pin "4") (pinfunction "CLK_4") (pintype "input"))
      (node (ref "IC2") (pin "44") (pinfunction "EECLK_44") (pintype "output"))
    )
    (net (code "68") (name "Net-(IC1-CS)") (class "Default")
      (node (ref "IC1") (pin "5") (pinfunction "CS_5") (pintype "input"))
      (node (ref "IC2") (pin "45") (pinfunction "EECS_45") (pintype "bidirectional"))
    )
    (net (code "69") (name "Net-(IC1-DI)") (class "Default")
      (node (ref "IC1") (pin "3") (pinfunction "DI_3") (pintype "input"))
      (node (ref "IC2") (pin "43") (pinfunction "EEDATA_43") (pintype "bidirectional"))
      (node (ref "R10") (pin "1") (pinfunction "1_1") (pintype "passive"))
    )
    (net (code "70") (name "Net-(IC1-DO)") (class "Default")
      (node (ref "IC1") (pin "1") (pinfunction "DO_1") (pintype "tri_state"))
      (node (ref "R10") (pin "2") (pinfunction "2_2") (pintype "passive"))
    )
    (net (code "71") (name "Net-(IC2-OSCIN)") (class "Default")
      (node (ref "IC2") (pin "1") (pinfunction "OSCIN_1") (pintype "input"))
      (node (ref "Q1") (pin "1") (pinfunction "1_1") (pintype "passive"))
    )
    (net (code "72") (name "Net-(IC2-REF)") (class "Default")
      (node (ref "IC2") (pin "5") (pinfunction "REF_5") (pintype "input"))
      (node (ref "R6") (pin "1") (pinfunction "1_1") (pintype "passive"))
    )
    (net (code "73") (name "Net-(IC2-VCCA)") (class "Default")
      (node (ref "C3") (pin "1") (pinfunction "1_1") (pintype "passive"))
      (node (ref "IC2") (pin "37") (pinfunction "VCCA_37") (pintype "power_in"))
    )
    (net (code "74") (name "Net-(LED1-PadA)") (class "Default")
      (node (ref "LED1") (pin "A") (pinfunction "A_A") (pintype "passive"))
      (node (ref "R8") (pin "2") (pinfunction "2_2") (pintype "passive"))
    )
    (net (code "75") (name "Net-(LED2-PadA)") (class "Default")
      (node (ref "LED2") (pin "A") (pinfunction "A_A") (pintype "passive"))
      (node (ref "R9") (pin "2") (pinfunction "2_2") (pintype "passive"))
    )
    (net (code "76") (name "Net-(R13-Pad1)") (class "Default")
      (node (ref "R13") (pin "1") (pinfunction "1_1") (pintype "passive"))
      (node (ref "U3") (pin "7") (pinfunction "7_7") (pintype "bidirectional"))
    )
    (net (code "77") (name "Net-(R14-Pad1)") (class "Default")
      (node (ref "R14") (pin "1") (pinfunction "1_1") (pintype "passive"))
      (node (ref "U3") (pin "3") (pinfunction "3_3") (pintype "bidirectional"))
    )
    (net (code "78") (name "Net-(R15-Pad1)") (class "Default")
      (node (ref "R15") (pin "1") (pinfunction "1_1") (pintype "passive"))
      (node (ref "R5") (pin "1") (pinfunction "1_1") (pintype "passive"))
      (node (ref "U3") (pin "1") (pinfunction "1_1") (pintype "bidirectional"))
    )
    (net (code "79") (name "OSC_OUT") (class "Default")
      (node (ref "IC2") (pin "2") (pinfunction "OSCOUT_2") (pintype "output"))
      (node (ref "J8") (pin "1") (pinfunction "1_1") (pintype "bidirectional"))
      (node (ref "Q1") (pin "3") (pinfunction "3_3") (pintype "passive"))
    )
    (net (code "80") (name "VCC") (class "Default")
      (node (ref "C4") (pin "1") (pinfunction "1_1") (pintype "passive"))
      (node (ref "R1") (pin "2") (pinfunction "2_2") (pintype "passive"))
      (node (ref "U4") (pin "30") (pinfunction "30_30") (pintype "bidirectional"))
      (node (ref "U4") (pin "5") (pinfunction "5_5") (pintype "bidirectional"))
    )
    (net (code "81") (name "VCCIO2") (class "Default")
      (node (ref "J2") (pin "2") (pinfunction "2_2") (pintype "passive"))
      (node (ref "J3") (pin "1") (pinfunction "1_1") (pintype "passive"))
      (node (ref "U4") (pin "1") (pinfunction "1_1") (pintype "bidirectional"))
    )
    (net (code "82") (name "VCCIO3") (class "Default")
      (node (ref "C8") (pin "1") (pinfunction "1_1") (pintype "passive"))
      (node (ref "J4") (pin "1") (pinfunction "1_1") (pintype "passive"))
      (node (ref "J5") (pin "2") (pinfunction "2_2") (pintype "passive"))
      (node (ref "U4") (pin "33") (pinfunction "33_33") (pintype "bidirectional"))
    )
    (net (code "83") (name "unconnected-(J1-ID-Pad4)") (class "Default")
      (node (ref "J1") (pin "4") (pinfunction "ID_4") (pintype "bidirectional"))
    )
  )
)
